# Sheet1.net
KiCad netlist of a schematic drawn in Altium Designer
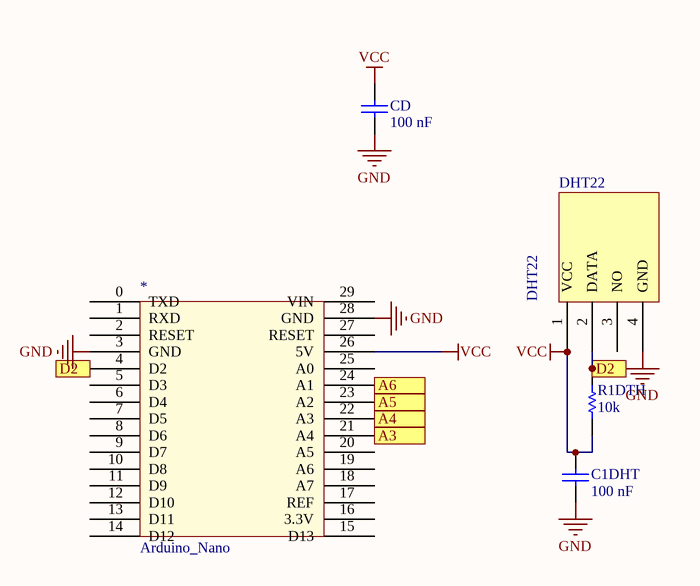
[diagram p0: Sheet1.SchDoc]

(export (version "E")
  (design (tool "Eeschema 10.0.6"))
  (components
    (comp (ref "*")
      (value "Arduino_Nano")
      (footprint "Arduino Nano SMD")
      (libsource (lib "AcqBoxLib") (part "Arduino_Nano"))
    )
    (comp (ref "C1DHT")
      (value "100 nF")
      (footprint "CAP 0805")
      (libsource (lib "AcqBoxLib") (part "CAP 0805"))
    )
    (comp (ref "CD") (value "100 nF") (footprint "CAP 0805") (libsource (lib "AcqBoxLib") (part "CAP 0805")))
    (comp (ref "DHT22")
      (value "DHT22")
      (footprint "DHT22 - 90deg SMD")
      (libsource (lib "AcqBoxLib") (part "DHT22"))
    )
    (comp (ref "R1DTH")
      (value "10k")
      (footprint "RES 0805")
      (description "SMD Resistor 0805")
      (fields (field (name "Comment") "RES 0805"))
      (libsource (lib "AcqBoxLib") (part "RES 0805"))
    )
  )
  (nets
    (net (code "1") (name "/A3") (class "Default")
      (node (ref "*") (pin "21") (pinfunction "A4_21") (pintype "passive"))
    )
    (net (code "2") (name "/A4") (class "Default")
      (node (ref "*") (pin "22") (pinfunction "A3_22") (pintype "passive"))
    )
    (net (code "3") (name "/A5") (class "Default")
      (node (ref "*") (pin "23") (pinfunction "A2_23") (pintype "passive"))
    )
    (net (code "4") (name "/A6") (class "Default")
      (node (ref "*") (pin "24") (pinfunction "A1_24") (pintype "passive"))
    )
    (net (code "5") (name "/D2") (class "Default")
      (node (ref "*") (pin "4") (pinfunction "D2_4") (pintype "passive"))
      (node (ref "DHT22") (pin "2") (pinfunction "DATA_2") (pintype "passive"))
      (node (ref "R1DTH") (pin "2") (pinfunction "2_2") (pintype "passive"))
    )
    (net (code "6") (name "GND") (class "Default")
      (node (ref "*") (pin "28") (pinfunction "GND_28") (pintype "passive"))
      (node (ref "*") (pin "3") (pinfunction "GND_3") (pintype "passive"))
      (node (ref "C1DHT") (pin "1") (pinfunction "1_1") (pintype "passive"))
      (node (ref "CD") (pin "1") (pinfunction "1_1") (pintype "passive"))
      (node (ref "DHT22") (pin "4") (pinfunction "GND_4") (pintype "passive"))
    )
    (net (code "7") (name "VCC") (class "Default")
      (node (ref "*") (pin "26") (pinfunction "5V_26") (pintype "passive"))
      (node (ref "C1DHT") (pin "2") (pinfunction "2_2") (pintype "passive"))
      (node (ref "CD") (pin "2") (pinfunction "2_2") (pintype "passive"))
      (node (ref "DHT22") (pin "1") (pinfunction "VCC_1") (pintype "passive"))
      (node (ref "R1DTH") (pin "1") (pinfunction "1_1") (pintype "passive"))
    )
    (net (code "8") (name "unconnected-(*-3.3V-Pad16)") (class "Default")
      (node (ref "*") (pin "16") (pinfunction "3.3V_16") (pintype "passive"))
    )
    (net (code "9") (name "unconnected-(*-A0-Pad25)") (class "Default")
      (node (ref "*") (pin "25") (pinfunction "A0_25") (pintype "passive"))
    )
    (net (code "10") (name "unconnected-(*-A5-Pad20)") (class "Default")
      (node (ref "*") (pin "20") (pinfunction "A5_20") (pintype "passive"))
    )
    (net (code "11") (name "unconnected-(*-A6-Pad19)") (class "Default")
      (node (ref "*") (pin "19") (pinfunction "A6_19") (pintype "passive"))
    )
    (net (code "12") (name "unconnected-(*-A7-Pad18)") (class "Default")
      (node (ref "*") (pin "18") (pinfunction "A7_18") (pintype "passive"))
    )
    (net (code "13") (name "unconnected-(*-D3-Pad5)") (class "Default")
      (node (ref "*") (pin "5") (pinfunction "D3_5") (pintype "passive"))
    )
    (net (code "14") (name "unconnected-(*-D4-Pad6)") (class "Default")
      (node (ref "*") (pin "6") (pinfunction "D4_6") (pintype "passive"))
    )
    (net (code "15") (name "unconnected-(*-D5-Pad7)") (class "Default")
      (node (ref "*") (pin "7") (pinfunction "D5_7") (pintype "passive"))
    )
    (net (code "16") (name "unconnected-(*-D6-Pad8)") (class "Default")
      (node (ref "*") (pin "8") (pinfunction "D6_8") (pintype "passive"))
    )
    (net (code "17") (name "unconnected-(*-D7-Pad9)") (class "Default")
      (node (ref "*") (pin "9") (pinfunction "D7_9") (pintype "passive"))
    )
    (net (code "18") (name "unconnected-(*-D8-Pad10)") (class "Default")
      (node (ref "*") (pin "10") (pinfunction "D8_10") (pintype "passive"))
    )
    (net (code "19") (name "unconnected-(*-D9-Pad11)") (class "Default")
      (node (ref "*") (pin "11") (pinfunction "D9_11") (pintype "passive"))
    )
    (net (code "20") (name "unconnected-(*-D10-Pad12)") (class "Default")
      (node (ref "*") (pin "12") (pinfunction "D10_12") (pintype "passive"))
    )
    (net (code "21") (name "unconnected-(*-D11-Pad13)") (class "Default")
      (node (ref "*") (pin "13") (pinfunction "D11_13") (pintype "passive"))
    )
    (net (code "22") (name "unconnected-(*-D12-Pad14)") (class "Default")
      (node (ref "*") (pin "14") (pinfunction "D12_14") (pintype "passive"))
    )
    (net (code "23") (name "unconnected-(*-D13-Pad15)") (class "Default")
      (node (ref "*") (pin "15") (pinfunction "D13_15") (pintype "passive"))
    )
    (net (code "24") (name "unconnected-(*-REF-Pad17)") (class "Default")
      (node (ref "*") (pin "17") (pinfunction "REF_17") (pintype "passive"))
    )
    (net (code "25") (name "unconnected-(*-RESET-Pad2)") (class "Default")
      (node (ref "*") (pin "2") (pinfunction "RESET_2") (pintype "passive"))
    )
    (net (code "26") (name "unconnected-(*-RESET-Pad27)") (class "Default")
      (node (ref "*") (pin "27") (pinfunction "RESET_27") (pintype "passive"))
    )
    (net (code "27") (name "unconnected-(*-RXD-Pad1)") (class "Default")
      (node (ref "*") (pin "1") (pinfunction "RXD_1") (pintype "passive"))
    )
    (net (code "28") (name "unconnected-(*-TXD-Pad0)") (class "Default")
      (node (ref "*") (pin "0") (pinfunction "TXD_0") (pintype "passive"))
    )
    (net (code "29") (name "unconnected-(*-VIN-Pad29)") (class "Default")
      (node (ref "*") (pin "29") (pinfunction "VIN_29") (pintype "passive"))
    )
    (net (code "30") (name "unconnected-(DHT22-NO-Pad3)") (class "Default")
      (node (ref "DHT22") (pin "3") (pinfunction "NO_3") (pintype "passive"))
    )
  )
)
